# 240x240_v3.net
KiCad netlist of a schematic drawn in EAGLE
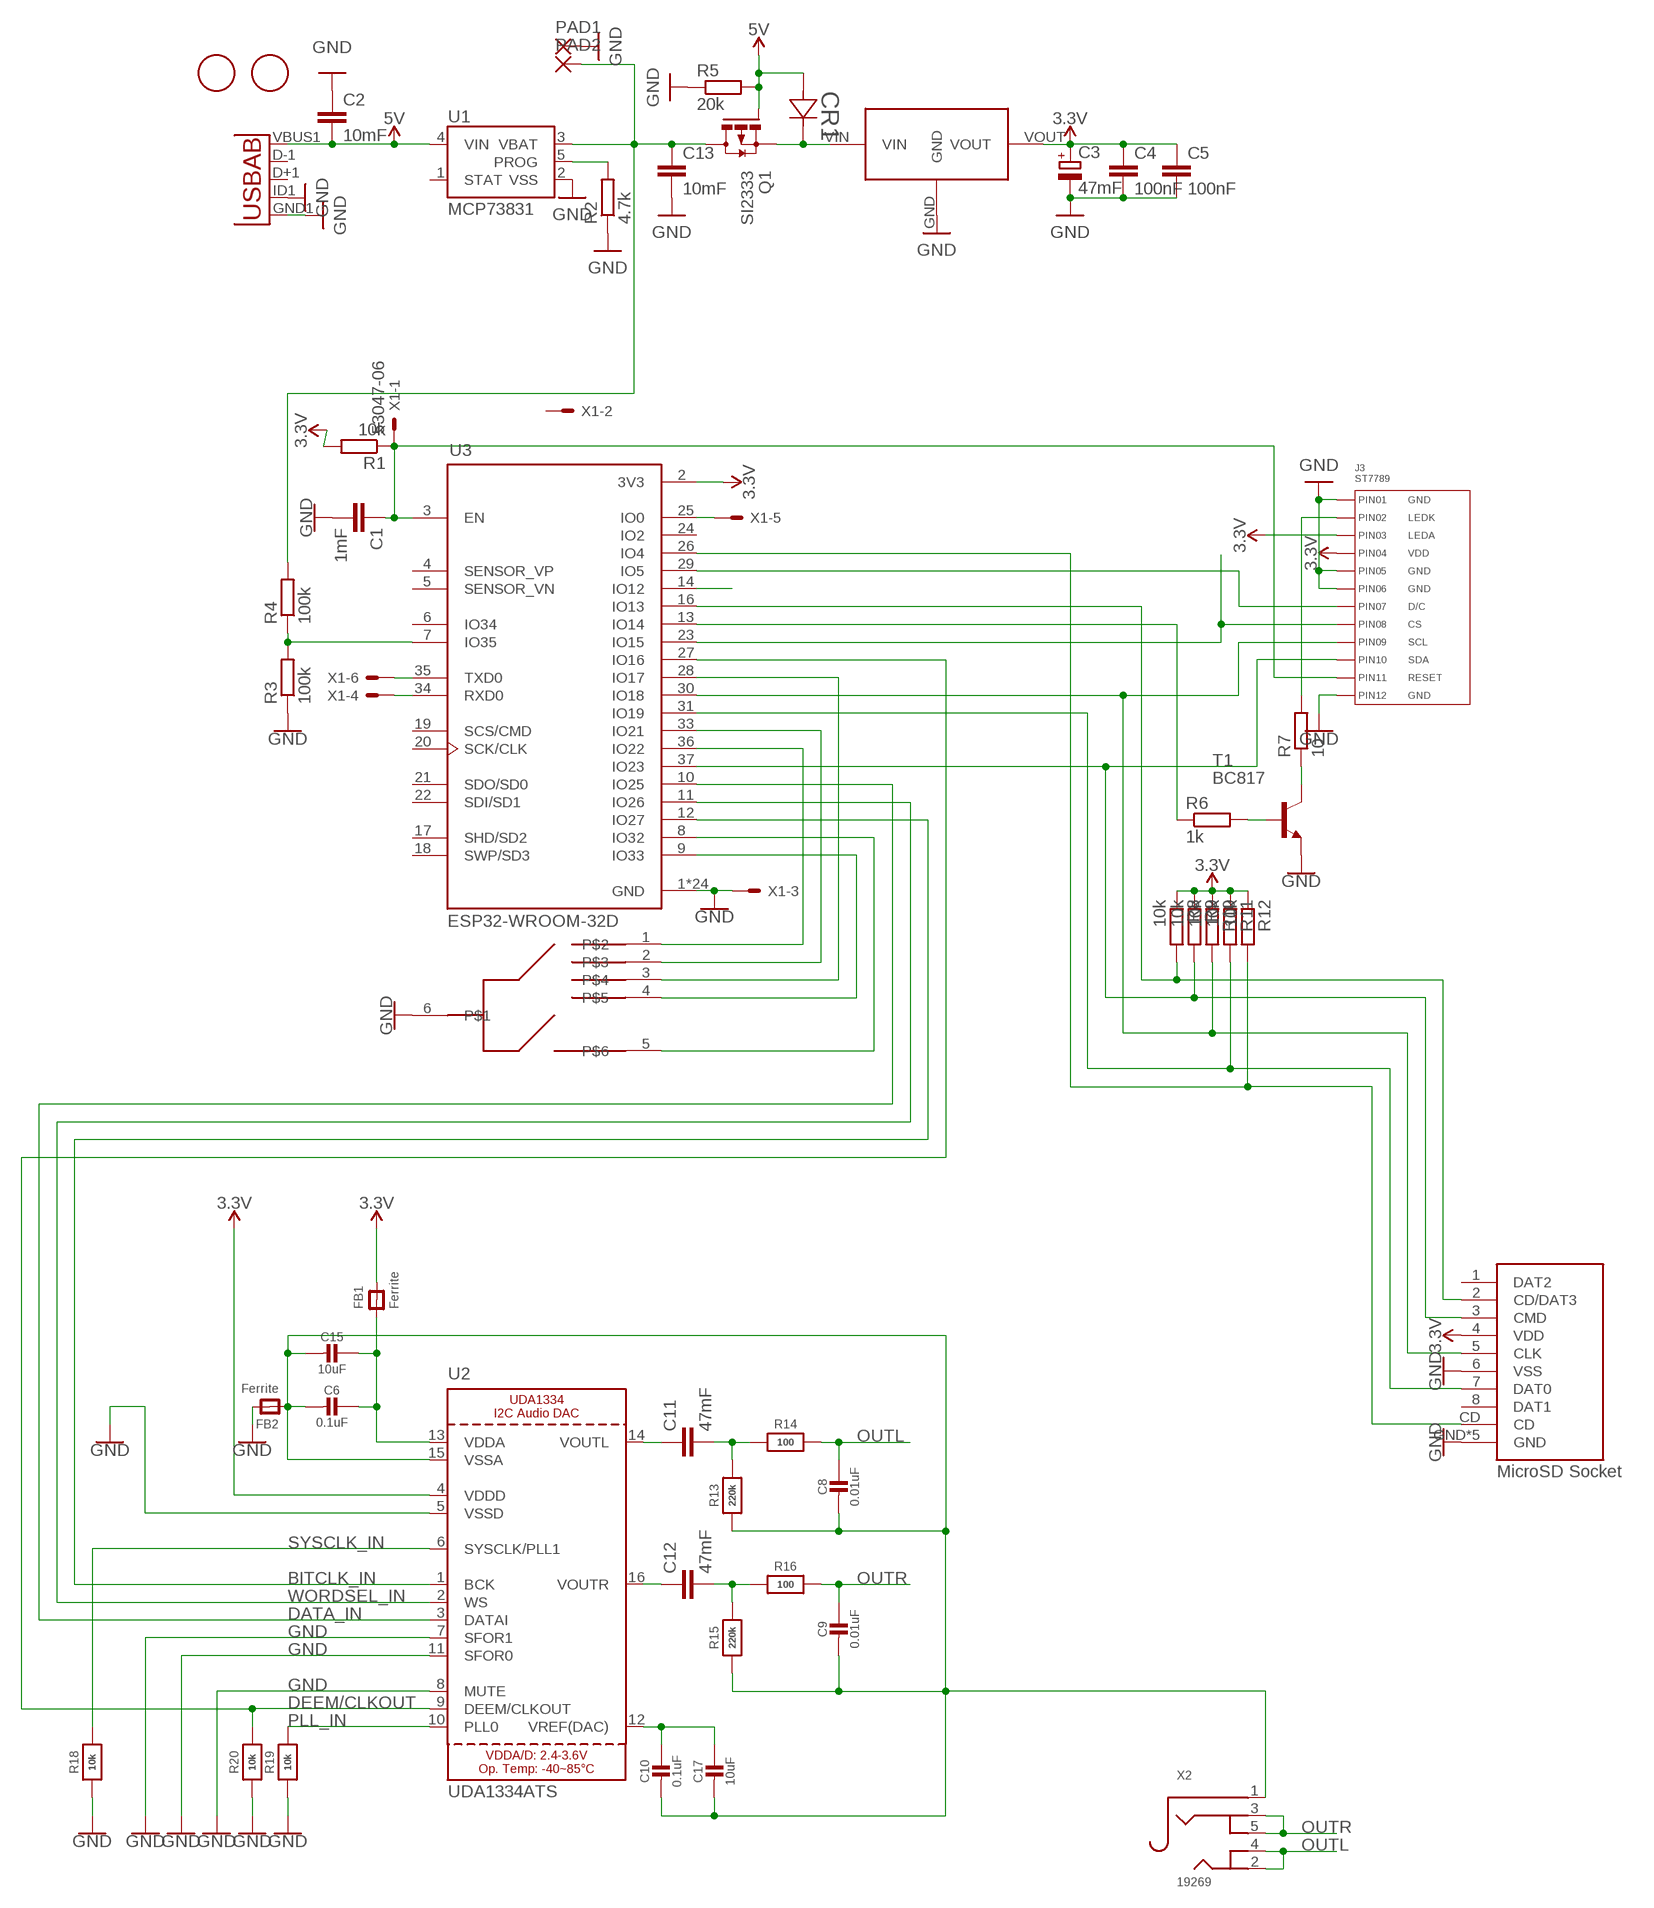
[diagram p0: schematic, sheet 1]

(export (version "E")
  (design (tool "Eeschema 10.0.6"))
  (components
    (comp (ref "C1")
      (value "1mF")
      (footprint "eagle-import:C0603")
      (libsource (lib "eagle-import") (part "C-EUC0603"))
    )
    (comp (ref "C2")
      (value "10mF")
      (footprint "eagle-import:C0603")
      (libsource (lib "eagle-import") (part "C-EUC0603"))
    )
    (comp (ref "C3")
      (value "47mF")
      (footprint "eagle-import:SMC_B")
      (libsource (lib "eagle-import") (part "CPOL-EUSMCB"))
    )
    (comp (ref "C4")
      (value "100nF")
      (footprint "eagle-import:C0805K")
      (libsource (lib "eagle-import") (part "C-EUC0805K"))
    )
    (comp (ref "C5")
      (value "100nF")
      (footprint "eagle-import:C0805K")
      (libsource (lib "eagle-import") (part "C-EUC0805K"))
    )
    (comp (ref "C6")
      (value "0.1uF")
      (footprint "eagle-import:0805-NO")
      (libsource (lib "eagle-import") (part "CAP_CERAMIC0805-NOOUTLINE"))
    )
    (comp (ref "C8")
      (value "0.01uF")
      (footprint "eagle-import:0805-NO")
      (libsource (lib "eagle-import") (part "CAP_CERAMIC0805-NOOUTLINE"))
    )
    (comp (ref "C9")
      (value "0.01uF")
      (footprint "eagle-import:0805-NO")
      (libsource (lib "eagle-import") (part "CAP_CERAMIC0805-NOOUTLINE"))
    )
    (comp (ref "C10")
      (value "0.1uF")
      (footprint "eagle-import:0805-NO")
      (libsource (lib "eagle-import") (part "CAP_CERAMIC0805-NOOUTLINE"))
    )
    (comp (ref "C11")
      (value "47mF")
      (footprint "eagle-import:C1210")
      (libsource (lib "eagle-import") (part "C-EUC1210"))
    )
    (comp (ref "C12")
      (value "47mF")
      (footprint "eagle-import:C1210")
      (libsource (lib "eagle-import") (part "C-EUC1210"))
    )
    (comp (ref "C13")
      (value "10mF")
      (footprint "eagle-import:C0603")
      (libsource (lib "eagle-import") (part "C-EUC0603"))
    )
    (comp (ref "C15")
      (value "10uF")
      (footprint "eagle-import:0805-NO")
      (libsource (lib "eagle-import") (part "CAP_CERAMIC0805-NOOUTLINE"))
    )
    (comp (ref "C17")
      (value "10uF")
      (footprint "eagle-import:0805-NO")
      (libsource (lib "eagle-import") (part "CAP_CERAMIC0805-NOOUTLINE"))
    )
    (comp (ref "CR1")
      (value "BAT48")
      (footprint "eagle-import:SOD-123_STM-M")
      (fields
        (field (name "MANUFACTURER_PART_NUMBER") "BAT48ZFILM")
        (field (name "COPYRIGHT") "Copyright (C) 2021 Ultra Librarian. All rights reserved.")
      )
      (libsource (lib "eagle-import") (part "BAT48ZFILMSOD-123_STM-M"))
    )
    (comp (ref "FB1")
      (value "Ferrite")
      (footprint "eagle-import:0805")
      (libsource (lib "eagle-import") (part "FERRITE0805"))
    )
    (comp (ref "FB2")
      (value "Ferrite")
      (footprint "eagle-import:0805")
      (libsource (lib "eagle-import") (part "FERRITE0805"))
    )
    (comp (ref "J3")
      (value "ST7789")
      (footprint "eagle-import:ST7789_CONNECTOR")
      (fields
        (field (name "LABEL01") "GND")
        (field (name "LABEL02") "LEDK")
        (field (name "LABEL03") "LEDA")
        (field (name "LABEL04") "VDD")
        (field (name "LABEL05") "GND")
        (field (name "LABEL06") "GND")
        (field (name "LABEL07") "D/C")
        (field (name "LABEL08") "CS")
        (field (name "LABEL09") "SCL")
        (field (name "LABEL10") "SDA")
        (field (name "LABEL11") "RESET")
        (field (name "LABEL12") "GND")
      )
      (libsource (lib "eagle-import") (part "CON_01X12_ST7789_CONNECTOR"))
    )
    (comp (ref "PAD1")
      (value "SMD2")
      (footprint "eagle-import:SMD1,27-2,54")
      (libsource (lib "eagle-import") (part "SMD2"))
    )
    (comp (ref "PAD2")
      (value "SMD2")
      (footprint "eagle-import:SMD1,27-2,54")
      (libsource (lib "eagle-import") (part "SMD2"))
    )
    (comp (ref "Q1")
      (value "SI2333")
      (footprint "eagle-import:SUPER-SOT3")
      (libsource (lib "eagle-import") (part "FDN360P"))
    )
    (comp (ref "R1")
      (value "10k")
      (footprint "eagle-import:R0603")
      (libsource (lib "eagle-import") (part "R-EU_R0603"))
    )
    (comp (ref "R2")
      (value "4.7k")
      (footprint "eagle-import:R0603")
      (libsource (lib "eagle-import") (part "R-EU_R0603"))
    )
    (comp (ref "R3")
      (value "100k")
      (footprint "eagle-import:R0805")
      (libsource (lib "eagle-import") (part "R-EU_R0805"))
    )
    (comp (ref "R4")
      (value "100k")
      (footprint "eagle-import:R0805")
      (libsource (lib "eagle-import") (part "R-EU_R0805"))
    )
    (comp (ref "R5")
      (value "20k")
      (footprint "eagle-import:R0603")
      (libsource (lib "eagle-import") (part "R-EU_R0603"))
    )
    (comp (ref "R6")
      (value "1k")
      (footprint "eagle-import:R0603")
      (libsource (lib "eagle-import") (part "R-EU_R0603"))
    )
    (comp (ref "R7")
      (value "10")
      (footprint "eagle-import:R0805")
      (libsource (lib "eagle-import") (part "R-EU_R0805"))
    )
    (comp (ref "R8")
      (value "10k")
      (footprint "eagle-import:R0603")
      (libsource (lib "eagle-import") (part "R-EU_R0603"))
    )
    (comp (ref "R9")
      (value "10k")
      (footprint "eagle-import:R0603")
      (libsource (lib "eagle-import") (part "R-EU_R0603"))
    )
    (comp (ref "R10")
      (value "10k")
      (footprint "eagle-import:R0603")
      (libsource (lib "eagle-import") (part "R-EU_R0603"))
    )
    (comp (ref "R11")
      (value "10k")
      (footprint "eagle-import:R0603")
      (libsource (lib "eagle-import") (part "R-EU_R0603"))
    )
    (comp (ref "R12")
      (value "10k")
      (footprint "eagle-import:R0603")
      (libsource (lib "eagle-import") (part "R-EU_R0603"))
    )
    (comp (ref "R13")
      (value "220k")
      (footprint "eagle-import:0805-NO")
      (libsource (lib "eagle-import") (part "RESISTOR0805_NOOUTLINE"))
    )
    (comp (ref "R14")
      (value "100")
      (footprint "eagle-import:0805-NO")
      (libsource (lib "eagle-import") (part "RESISTOR0805_NOOUTLINE"))
    )
    (comp (ref "R15")
      (value "220k")
      (footprint "eagle-import:0805-NO")
      (libsource (lib "eagle-import") (part "RESISTOR0805_NOOUTLINE"))
    )
    (comp (ref "R16")
      (value "100")
      (footprint "eagle-import:0805-NO")
      (libsource (lib "eagle-import") (part "RESISTOR0805_NOOUTLINE"))
    )
    (comp (ref "R18")
      (value "10k")
      (footprint "eagle-import:0603-NO")
      (libsource (lib "eagle-import") (part "RESISTOR_0603_NOOUT"))
    )
    (comp (ref "R19")
      (value "10k")
      (footprint "eagle-import:0603-NO")
      (libsource (lib "eagle-import") (part "RESISTOR_0603_NOOUT"))
    )
    (comp (ref "R20")
      (value "10k")
      (footprint "eagle-import:0603-NO")
      (libsource (lib "eagle-import") (part "RESISTOR_0603_NOOUT"))
    )
    (comp (ref "T1")
      (value "BC817")
      (footprint "eagle-import:SOT23-BEC")
      (libsource (lib "eagle-import") (part "-NPN-SOT23-BECBC817-16"))
    )
    (comp (ref "U$1")
      (value "XC6203")
      (footprint "eagle-import:SOT89")
      (libsource (lib "eagle-import") (part "HT7333"))
    )
    (comp (ref "U$2")
      (value "B5-P5S-0D")
      (footprint "eagle-import:B5-P5S-0D-Z")
      (libsource (lib "eagle-import") (part "B5-P5S-0D"))
    )
    (comp (ref "U$3")
      (value "FIDUCIAL")
      (footprint "eagle-import:FIDUCIAL_1MM")
      (libsource (lib "eagle-import") (part "FIDUCIAL"))
    )
    (comp (ref "U$4")
      (value "FIDUCIAL")
      (footprint "eagle-import:FIDUCIAL_1MM")
      (libsource (lib "eagle-import") (part "FIDUCIAL"))
    )
    (comp (ref "U$5")
      (value "ATTEND_MICROSD_SOCKET")
      (footprint "eagle-import:ATTEND_MICROSD_SOCKET")
      (libsource (lib "eagle-import") (part "ATTEND_MICROSD_SOCKET"))
    )
    (comp (ref "U1")
      (value "MCP73831")
      (footprint "eagle-import:SOT23-5")
      (libsource (lib "eagle-import") (part "MCP73831"))
    )
    (comp (ref "U2")
      (value "UDA1334ATS")
      (footprint "eagle-import:SSOP16_4.4MM")
      (libsource (lib "eagle-import") (part "AUDIO_I2S_UDA1334{dblquote}{dblquote}"))
    )
    (comp (ref "U3")
      (value "ESP32-WROOM-32D")
      (footprint "eagle-import:MODULE_ESP32-WROOM-32D")
      (fields (field (name "MF") "Espressif Systems"))
      (libsource (lib "eagle-import") (part "ESP32-WROOM-32D"))
    )
    (comp (ref "U4")
      (value "USB\"\"")
      (footprint "eagle-import:USB-MICRO-SMD")
      (libsource (lib "eagle-import") (part "USB{dblquote}{dblquote}"))
    )
    (comp (ref "X1")
      (value "53047-06")
      (footprint "eagle-import:53047-06")
      (fields (field (name "MF") "MOLEX") (field (name "MPN") "53047-0610-C"))
      (libsource (lib "eagle-import") (part "53?-06047"))
    )
    (comp (ref "X2")
      (value "19269")
      (footprint "eagle-import:4UCONN_19269")
      (libsource (lib "eagle-import") (part "AUDIO_3.5MMJACK"))
    )
  )
  (nets
    (net (code "1") (name "/BITCLK_IN") (class "Default")
      (node (ref "U2") (pin "1") (pinfunction "BCK_1") (pintype "input"))
      (node (ref "U3") (pin "12") (pinfunction "IO27_12") (pintype "bidirectional"))
    )
    (net (code "2") (name "/DATA_IN") (class "Default")
      (node (ref "U2") (pin "3") (pinfunction "DATAI_3") (pintype "input"))
      (node (ref "U3") (pin "10") (pinfunction "IO25_10") (pintype "bidirectional"))
    )
    (net (code "3") (name "/DEEM{slash}CLKOUT") (class "Default")
      (node (ref "R20") (pin "2") (pinfunction "2_2") (pintype "passive"))
      (node (ref "U2") (pin "9") (pinfunction "DEEM/CLKOUT_9") (pintype "bidirectional"))
      (node (ref "U3") (pin "27") (pinfunction "IO16_27") (pintype "bidirectional"))
    )
    (net (code "4") (name "/OUTL") (class "Default")
      (node (ref "C8") (pin "1") (pinfunction "1_1") (pintype "passive"))
      (node (ref "R14") (pin "2") (pinfunction "2_2") (pintype "passive"))
      (node (ref "X2") (pin "2") (pinfunction "P$5_2") (pintype "bidirectional"))
      (node (ref "X2") (pin "4") (pinfunction "P$4_4") (pintype "bidirectional"))
    )
    (net (code "5") (name "/OUTR") (class "Default")
      (node (ref "C9") (pin "1") (pinfunction "1_1") (pintype "passive"))
      (node (ref "R16") (pin "2") (pinfunction "2_2") (pintype "passive"))
      (node (ref "X2") (pin "3") (pinfunction "P$2_3") (pintype "bidirectional"))
      (node (ref "X2") (pin "5") (pinfunction "P$3_5") (pintype "bidirectional"))
    )
    (net (code "6") (name "/PLL_IN") (class "Default")
      (node (ref "R19") (pin "2") (pinfunction "2_2") (pintype "passive"))
      (node (ref "U2") (pin "10") (pinfunction "PLL0_10") (pintype "input"))
    )
    (net (code "7") (name "/SYSCLK_IN") (class "Default")
      (node (ref "R18") (pin "2") (pinfunction "2_2") (pintype "passive"))
      (node (ref "U2") (pin "6") (pinfunction "SYSCLK/PLL1_6") (pintype "input"))
    )
    (net (code "8") (name "/WORDSEL_IN") (class "Default")
      (node (ref "U2") (pin "2") (pinfunction "WS_2") (pintype "input"))
      (node (ref "U3") (pin "11") (pinfunction "IO26_11") (pintype "bidirectional"))
    )
    (net (code "9") (name "3.3V") (class "Default")
      (node (ref "C3") (pin "+") (pinfunction "+_+") (pintype "passive"))
      (node (ref "C4") (pin "1") (pinfunction "1_1") (pintype "passive"))
      (node (ref "C5") (pin "1") (pinfunction "1_1") (pintype "passive"))
      (node (ref "FB1") (pin "2") (pinfunction "P$2_2") (pintype "passive"))
      (node (ref "J3") (pin "P$3") (pinfunction "3_P$3") (pintype "bidirectional"))
      (node (ref "J3") (pin "P$4") (pinfunction "4_P$4") (pintype "bidirectional"))
      (node (ref "R1") (pin "2") (pinfunction "2_2") (pintype "passive"))
      (node (ref "R10") (pin "1") (pinfunction "1_1") (pintype "passive"))
      (node (ref "R11") (pin "1") (pinfunction "1_1") (pintype "passive"))
      (node (ref "R12") (pin "1") (pinfunction "1_1") (pintype "passive"))
      (node (ref "R8") (pin "1") (pinfunction "1_1") (pintype "passive"))
      (node (ref "R9") (pin "1") (pinfunction "1_1") (pintype "passive"))
      (node (ref "U$1") (pin "VOUT") (pinfunction "VOUT_VOUT") (pintype "bidirectional"))
      (node (ref "U$5") (pin "4") (pinfunction "VDD_4") (pintype "bidirectional"))
      (node (ref "U2") (pin "4") (pinfunction "VDDD_4") (pintype "power_in"))
      (node (ref "U3") (pin "2") (pinfunction "3V3_2") (pintype "power_in"))
    )
    (net (code "10") (name "5V") (class "Default")
      (node (ref "C2") (pin "2") (pinfunction "2_2") (pintype "passive"))
      (node (ref "CR1") (pin "1") (pinfunction "1_1") (pintype "passive"))
      (node (ref "Q1") (pin "1") (pinfunction "G_1") (pintype "passive"))
      (node (ref "R5") (pin "2") (pinfunction "2_2") (pintype "passive"))
      (node (ref "U1") (pin "4") (pinfunction "VIN_4") (pintype "power_in"))
      (node (ref "U4") (pin "VBUS1") (pinfunction "VBUS_VBUS1") (pintype "bidirectional"))
    )
    (net (code "11") (name "GND") (class "Default")
      (node (ref "C1") (pin "2") (pinfunction "2_2") (pintype "passive"))
      (node (ref "C13") (pin "2") (pinfunction "2_2") (pintype "passive"))
      (node (ref "C2") (pin "1") (pinfunction "1_1") (pintype "passive"))
      (node (ref "C3") (pin "-") (pinfunction "-_-") (pintype "passive"))
      (node (ref "C4") (pin "2") (pinfunction "2_2") (pintype "passive"))
      (node (ref "C5") (pin "2") (pinfunction "2_2") (pintype "passive"))
      (node (ref "FB2") (pin "2") (pinfunction "P$2_2") (pintype "passive"))
      (node (ref "J3") (pin "P$1") (pinfunction "1_P$1") (pintype "bidirectional"))
      (node (ref "J3") (pin "P$12") (pinfunction "12_P$12") (pintype "bidirectional"))
      (node (ref "J3") (pin "P$5") (pinfunction "5_P$5") (pintype "bidirectional"))
      (node (ref "J3") (pin "P$6") (pinfunction "6_P$6") (pintype "bidirectional"))
      (node (ref "PAD1") (pin "1") (pinfunction "P_1") (pintype "passive"))
      (node (ref "R18") (pin "1") (pinfunction "1_1") (pintype "passive"))
      (node (ref "R19") (pin "1") (pinfunction "1_1") (pintype "passive"))
      (node (ref "R2") (pin "1") (pinfunction "1_1") (pintype "passive"))
      (node (ref "R20") (pin "1") (pinfunction "1_1") (pintype "passive"))
      (node (ref "R3") (pin "1") (pinfunction "1_1") (pintype "passive"))
      (node (ref "R5") (pin "1") (pinfunction "1_1") (pintype "passive"))
      (node (ref "T1") (pin "E") (pinfunction "E_E") (pintype "passive"))
      (node (ref "U$1") (pin "GND") (pinfunction "GND_GND") (pintype "bidirectional"))
      (node (ref "U$2") (pin "6") (pinfunction "P$1_6") (pintype "bidirectional"))
      (node (ref "U$5") (pin "6") (pinfunction "VSS_6") (pintype "bidirectional"))
      (node (ref "U$5") (pin "GND") (pinfunction "GND_GND") (pintype "bidirectional"))
      (node (ref "U$5") (pin "GND2") (pinfunction "GND_GND2") (pintype "bidirectional"))
      (node (ref "U$5") (pin "GND3") (pinfunction "GND_GND3") (pintype "bidirectional"))
      (node (ref "U$5") (pin "GND4") (pinfunction "GND_GND4") (pintype "bidirectional"))
      (node (ref "U$5") (pin "GND5") (pinfunction "GND_GND5") (pintype "bidirectional"))
      (node (ref "U1") (pin "2") (pinfunction "VSS_2") (pintype "power_in"))
      (node (ref "U2") (pin "11") (pinfunction "SFOR0_11") (pintype "input"))
      (node (ref "U2") (pin "5") (pinfunction "VSSD_5") (pintype "power_in"))
      (node (ref "U2") (pin "7") (pinfunction "SFOR1_7") (pintype "input"))
      (node (ref "U2") (pin "8") (pinfunction "MUTE_8") (pintype "input"))
      (node (ref "U3") (pin "1") (pinfunction "GND_1") (pintype "power_in"))
      (node (ref "U3") (pin "15") (pinfunction "GND_15") (pintype "power_in"))
      (node (ref "U3") (pin "38") (pinfunction "GND_38") (pintype "power_in"))
      (node (ref "U3") (pin "39_1") (pinfunction "GND_39_1") (pintype "power_in"))
      (node (ref "U3") (pin "39_10") (pinfunction "GND_39_10") (pintype "power_in"))
      (node (ref "U3") (pin "39_11") (pinfunction "GND_39_11") (pintype "power_in"))
      (node (ref "U3") (pin "39_12") (pinfunction "GND_39_12") (pintype "power_in"))
      (node (ref "U3") (pin "39_13") (pinfunction "GND_39_13") (pintype "power_in"))
      (node (ref "U3") (pin "39_14") (pinfunction "GND_39_14") (pintype "power_in"))
      (node (ref "U3") (pin "39_15") (pinfunction "GND_39_15") (pintype "power_in"))
      (node (ref "U3") (pin "39_16") (pinfunction "GND_39_16") (pintype "power_in"))
      (node (ref "U3") (pin "39_17") (pinfunction "GND_39_17") (pintype "power_in"))
      (node (ref "U3") (pin "39_18") (pinfunction "GND_39_18") (pintype "power_in"))
      (node (ref "U3") (pin "39_19") (pinfunction "GND_39_19") (pintype "power_in"))
      (node (ref "U3") (pin "39_2") (pinfunction "GND_39_2") (pintype "power_in"))
      (node (ref "U3") (pin "39_20") (pinfunction "GND_39_20") (pintype "power_in"))
      (node (ref "U3") (pin "39_21") (pinfunction "GND_39_21") (pintype "power_in"))
      (node (ref "U3") (pin "39_3") (pinfunction "GND_39_3") (pintype "power_in"))
      (node (ref "U3") (pin "39_4") (pinfunction "GND_39_4") (pintype "power_in"))
      (node (ref "U3") (pin "39_5") (pinfunction "GND_39_5") (pintype "power_in"))
      (node (ref "U3") (pin "39_6") (pinfunction "GND_39_6") (pintype "power_in"))
      (node (ref "U3") (pin "39_7") (pinfunction "GND_39_7") (pintype "power_in"))
      (node (ref "U3") (pin "39_8") (pinfunction "GND_39_8") (pintype "power_in"))
      (node (ref "U3") (pin "39_9") (pinfunction "GND_39_9") (pintype "power_in"))
      (node (ref "U4") (pin "GND1") (pinfunction "GND_GND1") (pintype "bidirectional"))
      (node (ref "U4") (pin "ID1") (pinfunction "USBID_ID1") (pintype "bidirectional"))
      (node (ref "X1") (pin "3") (pinfunction "S_3") (pintype "passive"))
    )
    (net (code "12") (name "Net-(C11-Pad2)") (class "Default")
      (node (ref "C11") (pin "2") (pinfunction "2_2") (pintype "passive"))
      (node (ref "R13") (pin "2") (pinfunction "2_2") (pintype "passive"))
      (node (ref "R14") (pin "1") (pinfunction "1_1") (pintype "passive"))
    )
    (net (code "13") (name "Net-(C12-Pad2)") (class "Default")
      (node (ref "C12") (pin "2") (pinfunction "2_2") (pintype "passive"))
      (node (ref "R15") (pin "2") (pinfunction "2_2") (pintype "passive"))
      (node (ref "R16") (pin "1") (pinfunction "1_1") (pintype "passive"))
    )
    (net (code "14") (name "Net-(FB1-P$1)") (class "Default")
      (node (ref "C15") (pin "1") (pinfunction "1_1") (pintype "passive"))
      (node (ref "C6") (pin "1") (pinfunction "1_1") (pintype "passive"))
      (node (ref "FB1") (pin "1") (pinfunction "P$1_1") (pintype "passive"))
      (node (ref "U2") (pin "13") (pinfunction "VDDA_13") (pintype "power_in"))
    )
    (net (code "15") (name "Net-(FB2-P$1)") (class "Default")
      (node (ref "C10") (pin "2") (pinfunction "2_2") (pintype "passive"))
      (node (ref "C15") (pin "2") (pinfunction "2_2") (pintype "passive"))
      (node (ref "C17") (pin "2") (pinfunction "2_2") (pintype "passive"))
      (node (ref "C6") (pin "2") (pinfunction "2_2") (pintype "passive"))
      (node (ref "C8") (pin "2") (pinfunction "2_2") (pintype "passive"))
      (node (ref "C9") (pin "2") (pinfunction "2_2") (pintype "passive"))
      (node (ref "FB2") (pin "1") (pinfunction "P$1_1") (pintype "passive"))
      (node (ref "R13") (pin "1") (pinfunction "1_1") (pintype "passive"))
      (node (ref "R15") (pin "1") (pinfunction "1_1") (pintype "passive"))
      (node (ref "U2") (pin "15") (pinfunction "VSSA_15") (pintype "power_in"))
      (node (ref "X2") (pin "1") (pinfunction "P$1_1") (pintype "bidirectional"))
    )
    (net (code "16") (name "Net-(J3-2)") (class "Default")
      (node (ref "J3") (pin "P$2") (pinfunction "2_P$2") (pintype "bidirectional"))
      (node (ref "R7") (pin "2") (pinfunction "2_2") (pintype "passive"))
    )
    (net (code "17") (name "Net-(J3-7)") (class "Default")
      (node (ref "J3") (pin "P$7") (pinfunction "7_P$7") (pintype "bidirectional"))
      (node (ref "U3") (pin "29") (pinfunction "IO5_29") (pintype "bidirectional"))
    )
    (net (code "18") (name "Net-(J3-8)") (class "Default")
      (node (ref "J3") (pin "P$8") (pinfunction "8_P$8") (pintype "bidirectional"))
      (node (ref "U3") (pin "23") (pinfunction "IO15_23") (pintype "bidirectional"))
    )
    (net (code "19") (name "Net-(J3-9)") (class "Default")
      (node (ref "J3") (pin "P$9") (pinfunction "9_P$9") (pintype "bidirectional"))
      (node (ref "R10") (pin "2") (pinfunction "2_2") (pintype "passive"))
      (node (ref "U$5") (pin "5") (pinfunction "CLK_5") (pintype "bidirectional"))
      (node (ref "U3") (pin "30") (pinfunction "IO18_30") (pintype "bidirectional"))
    )
    (net (code "20") (name "Net-(J3-10)") (class "Default")
      (node (ref "J3") (pin "P$10") (pinfunction "10_P$10") (pintype "bidirectional"))
      (node (ref "R9") (pin "2") (pinfunction "2_2") (pintype "passive"))
      (node (ref "U$5") (pin "3") (pinfunction "CMD_3") (pintype "bidirectional"))
      (node (ref "U3") (pin "37") (pinfunction "IO23_37") (pintype "bidirectional"))
    )
    (net (code "21") (name "Net-(J3-11)") (class "Default")
      (node (ref "C1") (pin "1") (pinfunction "1_1") (pintype "passive"))
      (node (ref "J3") (pin "P$11") (pinfunction "11_P$11") (pintype "bidirectional"))
      (node (ref "R1") (pin "1") (pinfunction "1_1") (pintype "passive"))
      (node (ref "U3") (pin "3") (pinfunction "EN_3") (pintype "input"))
      (node (ref "X1") (pin "1") (pinfunction "S_1") (pintype "passive"))
    )
    (net (code "22") (name "Net-(PAD2-P)") (class "Default")
      (node (ref "C13") (pin "1") (pinfunction "1_1") (pintype "passive"))
      (node (ref "PAD2") (pin "1") (pinfunction "P_1") (pintype "passive"))
      (node (ref "Q1") (pin "3") (pinfunction "D_3") (pintype "passive"))
      (node (ref "R4") (pin "2") (pinfunction "2_2") (pintype "passive"))
      (node (ref "U1") (pin "3") (pinfunction "VBAT_3") (pintype "power_in"))
    )
    (net (code "23") (name "Net-(Q1-S)") (class "Default")
      (node (ref "CR1") (pin "2") (pinfunction "2_2") (pintype "passive"))
      (node (ref "Q1") (pin "2") (pinfunction "S_2") (pintype "passive"))
      (node (ref "U$1") (pin "VIN") (pinfunction "VIN_VIN") (pintype "bidirectional"))
    )
    (net (code "24") (name "Net-(R6-Pad2)") (class "Default")
      (node (ref "R6") (pin "2") (pinfunction "2_2") (pintype "passive"))
      (node (ref "T1") (pin "B") (pinfunction "B_B") (pintype "passive"))
    )
    (net (code "25") (name "Net-(R7-Pad1)") (class "Default")
      (node (ref "R7") (pin "1") (pinfunction "1_1") (pintype "passive"))
      (node (ref "T1") (pin "C") (pinfunction "C_C") (pintype "passive"))
    )
    (net (code "26") (name "Net-(U$2-P$2)") (class "Default")
      (node (ref "U$2") (pin "1") (pinfunction "P$2_1") (pintype "bidirectional"))
      (node (ref "U3") (pin "36") (pinfunction "IO22_36") (pintype "bidirectional"))
    )
    (net (code "27") (name "Net-(U$2-P$3)") (class "Default")
      (node (ref "U$2") (pin "2") (pinfunction "P$3_2") (pintype "bidirectional"))
      (node (ref "U3") (pin "33") (pinfunction "IO21_33") (pintype "bidirectional"))
    )
    (net (code "28") (name "Net-(U$2-P$4)") (class "Default")
      (node (ref "U$2") (pin "3") (pinfunction "P$4_3") (pintype "bidirectional"))
      (node (ref "U3") (pin "28") (pinfunction "IO17_28") (pintype "bidirectional"))
    )
    (net (code "29") (name "Net-(U$2-P$5)") (class "Default")
      (node (ref "U$2") (pin "4") (pinfunction "P$5_4") (pintype "bidirectional"))
      (node (ref "U3") (pin "9") (pinfunction "IO33_9") (pintype "bidirectional"))
    )
    (net (code "30") (name "Net-(U$2-P$6)") (class "Default")
      (node (ref "U$2") (pin "5") (pinfunction "P$6_5") (pintype "bidirectional"))
      (node (ref "U3") (pin "8") (pinfunction "IO32_8") (pintype "bidirectional"))
    )
    (net (code "31") (name "Net-(U$5-CD{slash}DAT3)") (class "Default")
      (node (ref "R8") (pin "2") (pinfunction "2_2") (pintype "passive"))
      (node (ref "U$5") (pin "2") (pinfunction "CD/DAT3_2") (pintype "bidirectional"))
      (node (ref "U3") (pin "16") (pinfunction "IO13_16") (pintype "bidirectional"))
    )
    (net (code "32") (name "Net-(U$5-DAT0)") (class "Default")
      (node (ref "R11") (pin "2") (pinfunction "2_2") (pintype "passive"))
      (node (ref "U$5") (pin "7") (pinfunction "DAT0_7") (pintype "bidirectional"))
      (node (ref "U3") (pin "31") (pinfunction "IO19_31") (pintype "bidirectional"))
    )
    (net (code "33") (name "Net-(U1-PROG)") (class "Default")
      (node (ref "R2") (pin "2") (pinfunction "2_2") (pintype "passive"))
      (node (ref "U1") (pin "5") (pinfunction "PROG_5") (pintype "input"))
    )
    (net (code "34") (name "Net-(U2-VOUTL)") (class "Default")
      (node (ref "C11") (pin "1") (pinfunction "1_1") (pintype "passive"))
      (node (ref "U2") (pin "14") (pinfunction "VOUTL_14") (pintype "output"))
    )
    (net (code "35") (name "Net-(U2-VOUTR)") (class "Default")
      (node (ref "C12") (pin "1") (pinfunction "1_1") (pintype "passive"))
      (node (ref "U2") (pin "16") (pinfunction "VOUTR_16") (pintype "output"))
    )
    (net (code "36") (name "Net-(U2-VREF(DAC))") (class "Default")
      (node (ref "C10") (pin "1") (pinfunction "1_1") (pintype "passive"))
      (node (ref "C17") (pin "1") (pinfunction "1_1") (pintype "passive"))
      (node (ref "U2") (pin "12") (pinfunction "VREF(DAC)_12") (pintype "output"))
    )
    (net (code "37") (name "Net-(U3-IO0)") (class "Default")
      (node (ref "U3") (pin "25") (pinfunction "IO0_25") (pintype "bidirectional"))
      (node (ref "X1") (pin "5") (pinfunction "S_5") (pintype "passive"))
    )
    (net (code "38") (name "Net-(U3-IO4)") (class "Default")
      (node (ref "R12") (pin "2") (pinfunction "2_2") (pintype "passive"))
      (node (ref "U$5") (pin "CD") (pinfunction "CD_CD") (pintype "bidirectional"))
      (node (ref "U3") (pin "26") (pinfunction "IO4_26") (pintype "bidirectional"))
    )
    (net (code "39") (name "Net-(U3-IO14)") (class "Default")
      (node (ref "R6") (pin "1") (pinfunction "1_1") (pintype "passive"))
      (node (ref "U3") (pin "13") (pinfunction "IO14_13") (pintype "bidirectional"))
    )
    (net (code "40") (name "Net-(U3-IO35)") (class "Default")
      (node (ref "R3") (pin "2") (pinfunction "2_2") (pintype "passive"))
      (node (ref "R4") (pin "1") (pinfunction "1_1") (pintype "passive"))
      (node (ref "U3") (pin "7") (pinfunction "IO35_7") (pintype "input"))
    )
    (net (code "41") (name "Net-(U3-RXD0)") (class "Default")
      (node (ref "U3") (pin "34") (pinfunction "RXD0_34") (pintype "bidirectional"))
      (node (ref "X1") (pin "4") (pinfunction "S_4") (pintype "passive"))
    )
    (net (code "42") (name "Net-(U3-TXD0)") (class "Default")
      (node (ref "U3") (pin "35") (pinfunction "TXD0_35") (pintype "bidirectional"))
      (node (ref "X1") (pin "6") (pinfunction "S_6") (pintype "passive"))
    )
    (net (code "43") (name "unconnected-(U$5-DAT1-Pad8)") (class "Default")
      (node (ref "U$5") (pin "8") (pinfunction "DAT1_8") (pintype "bidirectional"))
    )
    (net (code "44") (name "unconnected-(U$5-DAT2-Pad1)") (class "Default")
      (node (ref "U$5") (pin "1") (pinfunction "DAT2_1") (pintype "bidirectional"))
    )
    (net (code "45") (name "unconnected-(U1-STAT-Pad1)") (class "Default")
      (node (ref "U1") (pin "1") (pinfunction "STAT_1") (pintype "output"))
    )
    (net (code "46") (name "unconnected-(U3-IO2-Pad24)") (class "Default")
      (node (ref "U3") (pin "24") (pinfunction "IO2_24") (pintype "bidirectional"))
    )
    (net (code "47") (name "unconnected-(U3-IO12-Pad14)") (class "Default")
      (node (ref "U3") (pin "14") (pinfunction "IO12_14") (pintype "bidirectional"))
    )
    (net (code "48") (name "unconnected-(U3-IO34-Pad6)") (class "Default")
      (node (ref "U3") (pin "6") (pinfunction "IO34_6") (pintype "input"))
    )
    (net (code "49") (name "unconnected-(U3-SCK{slash}CLK-Pad20)") (class "Default")
      (node (ref "U3") (pin "20") (pinfunction "SCK/CLK_20") (pintype "bidirectional"))
    )
    (net (code "50") (name "unconnected-(U3-SCS{slash}CMD-Pad19)") (class "Default")
      (node (ref "U3") (pin "19") (pinfunction "SCS/CMD_19") (pintype "bidirectional"))
    )
    (net (code "51") (name "unconnected-(U3-SDI{slash}SD1-Pad22)") (class "Default")
      (node (ref "U3") (pin "22") (pinfunction "SDI/SD1_22") (pintype "bidirectional"))
    )
    (net (code "52") (name "unconnected-(U3-SDO{slash}SD0-Pad21)") (class "Default")
      (node (ref "U3") (pin "21") (pinfunction "SDO/SD0_21") (pintype "bidirectional"))
    )
    (net (code "53") (name "unconnected-(U3-SENSOR_VN-Pad5)") (class "Default")
      (node (ref "U3") (pin "5") (pinfunction "SENSOR_VN_5") (pintype "input"))
    )
    (net (code "54") (name "unconnected-(U3-SENSOR_VP-Pad4)") (class "Default")
      (node (ref "U3") (pin "4") (pinfunction "SENSOR_VP_4") (pintype "input"))
    )
    (net (code "55") (name "unconnected-(U3-SHD{slash}SD2-Pad17)") (class "Default")
      (node (ref "U3") (pin "17") (pinfunction "SHD/SD2_17") (pintype "bidirectional"))
    )
    (net (code "56") (name "unconnected-(U3-SWP{slash}SD3-Pad18)") (class "Default")
      (node (ref "U3") (pin "18") (pinfunction "SWP/SD3_18") (pintype "bidirectional"))
    )
    (net (code "57") (name "unconnected-(U4-D+-PadD+1)") (class "Default")
      (node (ref "U4") (pin "D+1") (pinfunction "D+_D+1") (pintype "bidirectional"))
    )
    (net (code "58") (name "unconnected-(U4-D--PadD-1)") (class "Default")
      (node (ref "U4") (pin "D-1") (pinfunction "D-_D-1") (pintype "bidirectional"))
    )
    (net (code "59") (name "unconnected-(X1B-S-Pad2)") (class "Default")
      (node (ref "X1") (pin "2") (pinfunction "S_2") (pintype "passive"))
    )
  )
)
